# HV_DAC_8ch_FPGA_Config.net
KiCad netlist of a schematic drawn in Altium Designer
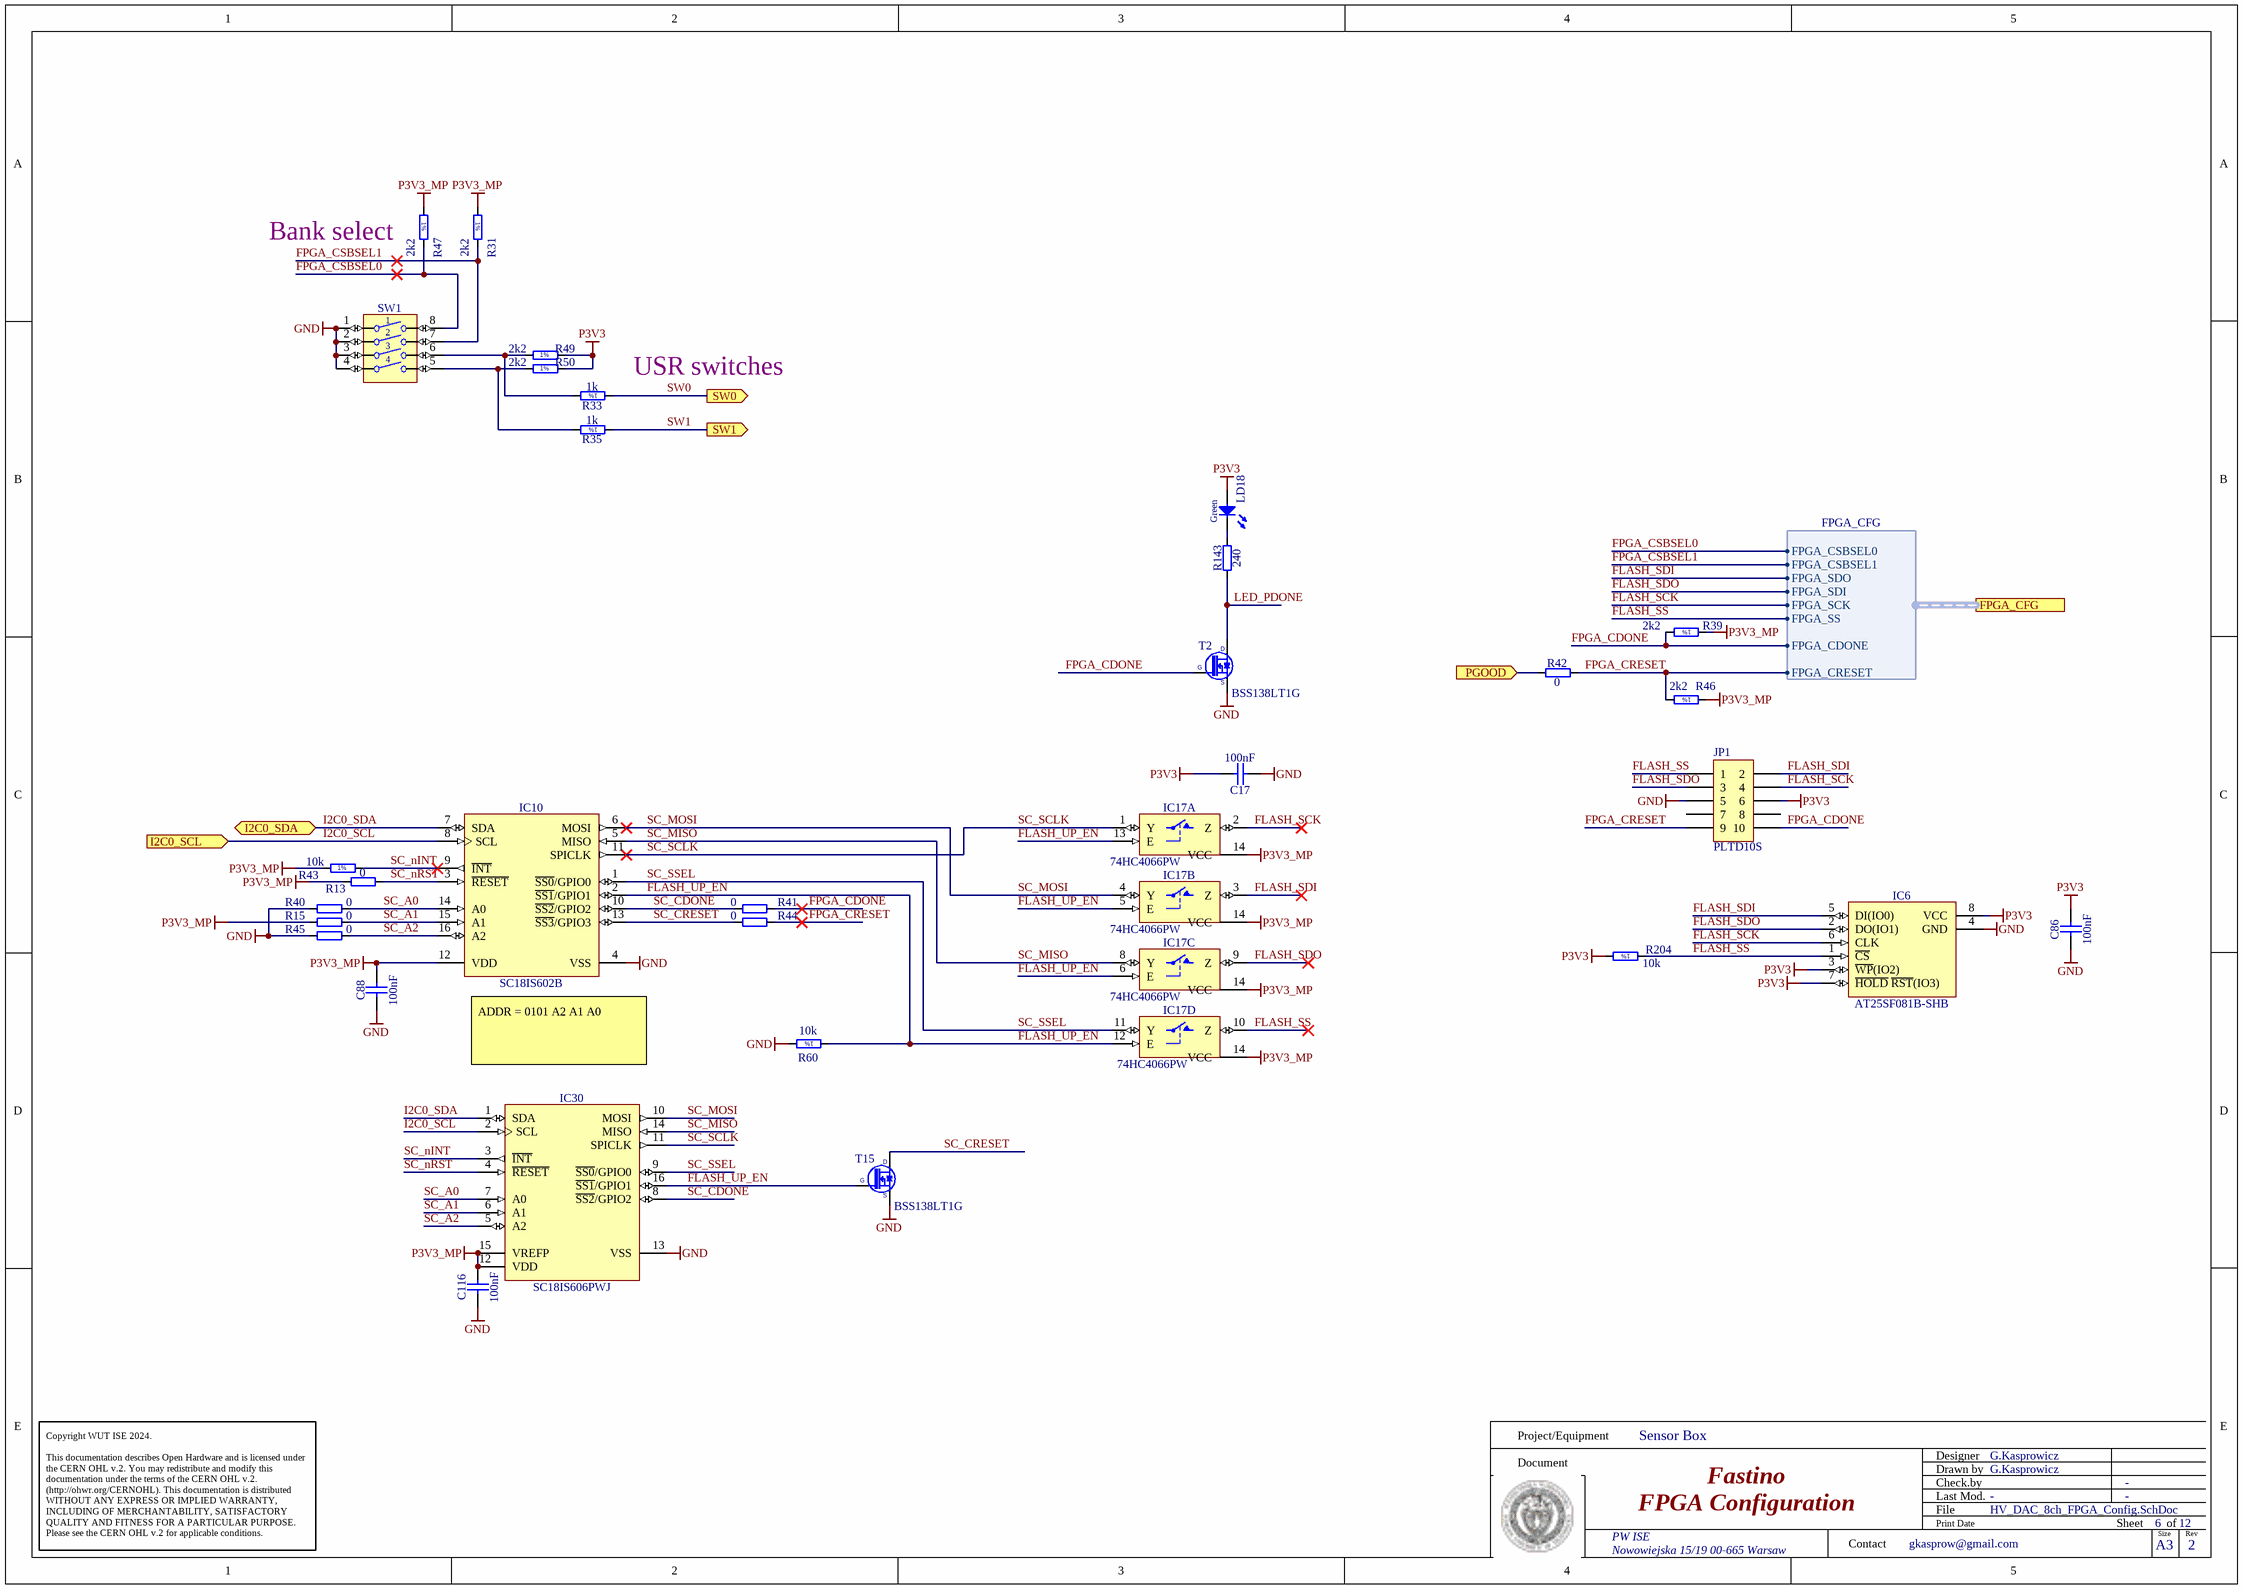
[diagram p0: HV_DAC_8ch_FPGA_Config.SchDoc]

(export (version "E")
  (design (tool "Eeschema 10.0.6"))
  (components
    (comp (ref "C17")
      (value "100nF")
      (footprint "CAPC1005X55N")
      (description "Non-polarised capacitor")
      (fields
        (field (name "PART NUMBER") "CC0402_100NF_16V_10%_X5R")
        (field (name "VOLTAGE") "16V")
        (field (name "AUTHOR") "CERN DEM JLC")
      )
      (libsource (lib "Capacitors") (part "Capacitor - non polarized"))
    )
    (comp (ref "C86")
      (value "100nF")
      (footprint "CAPC1005X55N")
      (description "Non-polarised capacitor")
      (fields
        (field (name "PART NUMBER") "CC0402_100NF_16V_10%_X5R")
        (field (name "VOLTAGE") "16V")
        (field (name "AUTHOR") "CERN DEM JLC")
      )
      (libsource (lib "Capacitors") (part "Capacitor - non polarized"))
    )
    (comp (ref "C88")
      (value "100nF")
      (footprint "CAPC1005X55N")
      (description "Non-polarised capacitor")
      (fields
        (field (name "PART NUMBER") "CC0402_100NF_16V_10%_X5R")
        (field (name "VOLTAGE") "16V")
        (field (name "AUTHOR") "CERN DEM JLC")
      )
      (libsource (lib "Capacitors") (part "Capacitor - non polarized"))
    )
    (comp (ref "C116")
      (value "100nF")
      (footprint "CAPC1005X55N")
      (description "Non-polarised capacitor")
      (fields
        (field (name "PART NUMBER") "CC0402_100NF_16V_10%_X5R")
        (field (name "VOLTAGE") "16V")
        (field (name "AUTHOR") "CERN DEM JLC")
      )
      (libsource (lib "Capacitors") (part "Capacitor - non polarized"))
    )
    (comp (ref "IC6")
      (value "AT25SF081B-SHB")
      (footprint "SOIC127P790X216-8N")
      (description "8M-bit Serial Flash Memory with uniform 4KB sectors and Dual/Quad SPI and QPI")
      (fields (field (name "MANUFACTURER") "Renesas") (field (name "AUTHOR") "GK"))
      (libsource (lib "ICS-logic") (part "MEM_AT25SF081B-SHB"))
    )
    (comp (ref "IC10")
      (value "SC18IS602B")
      (footprint "SOP65P640X110-16N")
      (description "I2C-bus to SPI bridge")
      (fields (field (name "MANUFACTURER") "NXP SEMICONDUCTORS") (field (name "AUTHOR") "CERN DEM MR"))
      (libsource (lib "ICs And Semiconductors") (part "SC18IS602B"))
    )
    (comp (ref "IC17")
      (value "74HC4066PW")
      (footprint "SOP65P640X110-14N")
      (fields (field (name "MANUFACTURER") "NXP SEMICONDUCTORS") (field (name "AUTHOR") "CERN DEM JLC"))
      (libsource (lib "ICs And Semiconductors") (part "4066"))
    )
    (comp (ref "IC30")
      (value "SC18IS606PWJ")
      (footprint "SOP65P640X110-16N")
      (description "I2C-bus to SPI bridge")
      (fields (field (name "MANUFACTURER") "NXP SEMICONDUCTORS") (field (name "AUTHOR") "GK"))
      (libsource (lib "ICS-logic") (part "SC18IS606PWJ"))
    )
    (comp (ref "JP1")
      (value "PLTD10S")
      (footprint "PLTD10S")
      (description "Goldpin 2.54mm, male header")
      (fields (field (name "MANUFACTURER") "Maritex"))
      (libsource (lib "LIBRARY_SCH") (part "CON_2x5 2.54 male SMT"))
    )
    (comp (ref "LD18")
      (value "Green")
      (footprint "LED_AVAGO_HSME-C120")
      (description "LED Green 1C 2A")
      (fields
        (field (name "PART NUMBER") "LED_AVAGO_HSME-C120")
        (field (name "MANUFACTURER") "AVAGO TECHNOLOGIES")
        (field (name "AUTHOR") "CERN DEM JMW")
      )
      (libsource (lib "ICs And Semiconductors") (part "LED Green 1C 2A"))
    )
    (comp (ref "R13")
      (value "0")
      (footprint "RESC1005X40N")
      (description "Resistor")
      (fields
        (field (name "PART NUMBER") "R0402_0R_JUMPER")
        (field (name "MANUFACTURER") "GENERIC")
        (field (name "AUTHOR") "CERN DEM JLC")
      )
      (libsource (lib "Resistors") (part "Resistor"))
    )
    (comp (ref "R15")
      (value "0")
      (footprint "RESC1005X40N")
      (description "Resistor")
      (fields
        (field (name "PART NUMBER") "R0402_0R_JUMPER")
        (field (name "MANUFACTURER") "GENERIC")
        (field (name "AUTHOR") "CERN DEM JLC")
      )
      (libsource (lib "Resistors") (part "Resistor"))
    )
    (comp (ref "R31")
      (value "2k2")
      (footprint "RESC1005X40N")
      (description "Resistor - 1%")
      (fields
        (field (name "PART NUMBER") "R0402_2K2_1%_0.0625W_100PPM")
        (field (name "POWER") "0.0625W")
        (field (name "AUTHOR") "CERN DEM JLC")
      )
      (libsource (lib "Resistors") (part "Resistor - 1%"))
    )
    (comp (ref "R33")
      (value "1k")
      (footprint "RESC1005X40N")
      (description "Resistor - 1%")
      (fields
        (field (name "PART NUMBER") "R0402_1K_1%_0.0625W_100PPM")
        (field (name "POWER") "0.0625W")
        (field (name "AUTHOR") "CERN DEM JLC")
      )
      (libsource (lib "Resistors") (part "Resistor - 1%"))
    )
    (comp (ref "R35")
      (value "1k")
      (footprint "RESC1005X40N")
      (description "Resistor - 1%")
      (fields
        (field (name "PART NUMBER") "R0402_1K_1%_0.0625W_100PPM")
        (field (name "POWER") "0.0625W")
        (field (name "AUTHOR") "CERN DEM JLC")
      )
      (libsource (lib "Resistors") (part "Resistor - 1%"))
    )
    (comp (ref "R39")
      (value "2k2")
      (footprint "RESC1005X40N")
      (description "Resistor - 1%")
      (fields
        (field (name "PART NUMBER") "R0402_2K2_1%_0.0625W_100PPM")
        (field (name "POWER") "0.0625W")
        (field (name "AUTHOR") "CERN DEM JLC")
      )
      (libsource (lib "Resistors") (part "Resistor - 1%"))
    )
    (comp (ref "R40")
      (value "0")
      (footprint "RESC1005X40N")
      (description "Resistor")
      (fields
        (field (name "PART NUMBER") "R0402_0R_JUMPER")
        (field (name "MANUFACTURER") "GENERIC")
        (field (name "AUTHOR") "CERN DEM JLC")
      )
      (libsource (lib "Resistors") (part "Resistor"))
    )
    (comp (ref "R41")
      (value "0")
      (footprint "RESC1005X40N")
      (description "Resistor")
      (fields
        (field (name "PART NUMBER") "R0402_0R_JUMPER")
        (field (name "MANUFACTURER") "GENERIC")
        (field (name "AUTHOR") "CERN DEM JLC")
      )
      (libsource (lib "Resistors") (part "Resistor"))
    )
    (comp (ref "R42")
      (value "0")
      (footprint "RESC1005X40N")
      (description "Resistor")
      (fields
        (field (name "PART NUMBER") "R0402_0R_JUMPER")
        (field (name "MANUFACTURER") "GENERIC")
        (field (name "AUTHOR") "CERN DEM JLC")
      )
      (libsource (lib "Resistors") (part "Resistor"))
    )
    (comp (ref "R43")
      (value "10k")
      (footprint "RESC1005X40N")
      (description "Resistor - 1%")
      (fields
        (field (name "PART NUMBER") "R0402_10K_1%_0.0625W_100PPM")
        (field (name "POWER") "0.0625W")
        (field (name "AUTHOR") "CERN DEM JLC")
      )
      (libsource (lib "Resistors") (part "Resistor - 1%"))
    )
    (comp (ref "R44")
      (value "0")
      (footprint "RESC1005X40N")
      (description "Resistor")
      (fields
        (field (name "PART NUMBER") "R0402_0R_JUMPER")
        (field (name "MANUFACTURER") "GENERIC")
        (field (name "AUTHOR") "CERN DEM JLC")
      )
      (libsource (lib "Resistors") (part "Resistor"))
    )
    (comp (ref "R45")
      (value "0")
      (footprint "RESC1005X40N")
      (description "Resistor")
      (fields
        (field (name "PART NUMBER") "R0402_0R_JUMPER")
        (field (name "MANUFACTURER") "GENERIC")
        (field (name "AUTHOR") "CERN DEM JLC")
      )
      (libsource (lib "Resistors") (part "Resistor"))
    )
    (comp (ref "R46")
      (value "2k2")
      (footprint "RESC1005X40N")
      (description "Resistor - 1%")
      (fields
        (field (name "PART NUMBER") "R0402_2K2_1%_0.0625W_100PPM")
        (field (name "POWER") "0.0625W")
        (field (name "AUTHOR") "CERN DEM JLC")
      )
      (libsource (lib "Resistors") (part "Resistor - 1%"))
    )
    (comp (ref "R47")
      (value "2k2")
      (footprint "RESC1005X40N")
      (description "Resistor - 1%")
      (fields
        (field (name "PART NUMBER") "R0402_2K2_1%_0.0625W_100PPM")
        (field (name "POWER") "0.0625W")
        (field (name "AUTHOR") "CERN DEM JLC")
      )
      (libsource (lib "Resistors") (part "Resistor - 1%"))
    )
    (comp (ref "R49")
      (value "2k2")
      (footprint "RESC1005X40N")
      (description "Resistor - 1%")
      (fields
        (field (name "PART NUMBER") "R0402_2K2_1%_0.0625W_100PPM")
        (field (name "POWER") "0.0625W")
        (field (name "AUTHOR") "CERN DEM JLC")
      )
      (libsource (lib "Resistors") (part "Resistor - 1%"))
    )
    (comp (ref "R50")
      (value "2k2")
      (footprint "RESC1005X40N")
      (description "Resistor - 1%")
      (fields
        (field (name "PART NUMBER") "R0402_2K2_1%_0.0625W_100PPM")
        (field (name "POWER") "0.0625W")
        (field (name "AUTHOR") "CERN DEM JLC")
      )
      (libsource (lib "Resistors") (part "Resistor - 1%"))
    )
    (comp (ref "R60")
      (value "10k")
      (footprint "RESC1005X40N")
      (description "Resistor - 1%")
      (fields
        (field (name "PART NUMBER") "R0402_10K_1%_0.0625W_100PPM")
        (field (name "POWER") "0.0625W")
        (field (name "AUTHOR") "CERN DEM JLC")
      )
      (libsource (lib "Resistors") (part "Resistor - 1%"))
    )
    (comp (ref "R143")
      (value "240")
      (footprint "RESC1005X40N")
      (description "Resistor - 1%")
      (fields
        (field (name "PART NUMBER") "R0402_240R_1%_0.0625W_100PPM")
        (field (name "POWER") "0.0625W")
        (field (name "AUTHOR") "CERN DEM JLC")
      )
      (libsource (lib "Resistors") (part "Resistor - 1%"))
    )
    (comp (ref "R204")
      (value "10k")
      (footprint "RESC1005X40N")
      (description "Resistor - 1%")
      (fields
        (field (name "PART NUMBER") "R0402_10K_1%_0.0625W_100PPM")
        (field (name "POWER") "0.0625W")
        (field (name "AUTHOR") "CERN DEM JLC")
      )
      (libsource (lib "Resistors") (part "Resistor - 1%"))
    )
    (comp (ref "SW1")
      (value "Switch")
      (footprint "SW_TYCO_1571983-4")
      (description "4 Ways SPST DIP Switch")
      (fields
        (field (name "PART NUMBER") "SW_TYCO_1571983-4")
        (field (name "MANUFACTURER") "TYCO")
        (field (name "AUTHOR") "CERN DEM JLC")
      )
      (libsource (lib "Eletro-mechanical") (part "SW 4x SPST DIP Switch"))
    )
    (comp (ref "T2")
      (value "BSS138LT1G")
      (footprint "SOT95P240X110-3N")
      (description "N-CHANNEL MOSFET WITH DIODE")
      (fields (field (name "MANUFACTURER") "ON SEMICONDUCTOR") (field (name "AUTHOR") "CERN DEM JLC"))
      (libsource (lib "ICs And Semiconductors") (part "N-MOSFET-D 1G 2S 3D"))
    )
    (comp (ref "T15")
      (value "BSS138LT1G")
      (footprint "SOT95P240X110-3N")
      (description "N-CHANNEL MOSFET WITH DIODE")
      (fields (field (name "MANUFACTURER") "ON SEMICONDUCTOR") (field (name "AUTHOR") "CERN DEM JLC"))
      (libsource (lib "ICs And Semiconductors") (part "N-MOSFET-D 1G 2S 3D"))
    )
  )
  (nets
    (net (code "2") (name "/FLASH_SCK") (class "Default")
      (node (ref "IC17") (pin "2") (pinfunction "Z_2") (pintype "bidirectional"))
      (node (ref "IC6") (pin "6") (pinfunction "CLK_6") (pintype "input"))
      (node (ref "JP1") (pin "4") (pinfunction "4_4") (pintype "passive"))
    )
    (net (code "3") (name "/FLASH_SDI") (class "Default")
      (node (ref "IC17") (pin "3") (pinfunction "Z_3") (pintype "bidirectional"))
      (node (ref "IC6") (pin "5") (pinfunction "DI(IO0)_5") (pintype "bidirectional"))
      (node (ref "JP1") (pin "2") (pinfunction "2_2") (pintype "passive"))
    )
    (net (code "4") (name "/FLASH_SDO") (class "Default")
      (node (ref "IC17") (pin "9") (pinfunction "Z_9") (pintype "bidirectional"))
      (node (ref "IC6") (pin "2") (pinfunction "DO(IO1)_2") (pintype "bidirectional"))
      (node (ref "JP1") (pin "3") (pinfunction "3_3") (pintype "passive"))
    )
    (net (code "5") (name "/FLASH_SS") (class "Default")
      (node (ref "IC17") (pin "10") (pinfunction "Z_10") (pintype "bidirectional"))
      (node (ref "IC6") (pin "1") (pinfunction "~{CS}_1") (pintype "input"))
      (node (ref "JP1") (pin "1") (pinfunction "1_1") (pintype "passive"))
      (node (ref "R204") (pin "1") (pinfunction "1_1") (pintype "passive"))
    )
    (net (code "6") (name "/FLASH_UP_EN") (class "Default")
      (node (ref "IC10") (pin "2") (pinfunction "~{SS1}/GPIO1_2") (pintype "bidirectional"))
      (node (ref "IC17") (pin "12") (pinfunction "E_12") (pintype "input"))
      (node (ref "IC17") (pin "13") (pinfunction "E_13") (pintype "input"))
      (node (ref "IC17") (pin "5") (pinfunction "E_5") (pintype "input"))
      (node (ref "IC17") (pin "6") (pinfunction "E_6") (pintype "input"))
      (node (ref "IC30") (pin "16") (pinfunction "~{SS1}/GPIO1_16") (pintype "bidirectional"))
      (node (ref "R60") (pin "1") (pinfunction "1_1") (pintype "passive"))
      (node (ref "T15") (pin "1") (pinfunction "G_1") (pintype "passive"))
    )
    (net (code "7") (name "/FPGA_CDONE") (class "Default")
      (node (ref "JP1") (pin "10") (pinfunction "10_10") (pintype "passive"))
      (node (ref "R39") (pin "2") (pinfunction "2_2") (pintype "passive"))
      (node (ref "R41") (pin "1") (pinfunction "1_1") (pintype "passive"))
      (node (ref "T2") (pin "1") (pinfunction "G_1") (pintype "passive"))
    )
    (net (code "8") (name "/FPGA_CRESET") (class "Default")
      (node (ref "JP1") (pin "9") (pinfunction "9_9") (pintype "passive"))
      (node (ref "R42") (pin "2") (pinfunction "2_2") (pintype "passive"))
      (node (ref "R44") (pin "1") (pinfunction "1_1") (pintype "passive"))
      (node (ref "R46") (pin "2") (pinfunction "2_2") (pintype "passive"))
    )
    (net (code "9") (name "/FPGA_CSBSEL0") (class "Default")
      (node (ref "R47") (pin "2") (pinfunction "2_2") (pintype "passive"))
      (node (ref "SW1") (pin "8") (pinfunction "8_8") (pintype "bidirectional"))
    )
    (net (code "10") (name "/FPGA_CSBSEL1") (class "Default")
      (node (ref "R31") (pin "2") (pinfunction "2_2") (pintype "passive"))
      (node (ref "SW1") (pin "7") (pinfunction "7_7") (pintype "bidirectional"))
    )
    (net (code "11") (name "/I2C0_SCL") (class "Default")
      (node (ref "IC10") (pin "8") (pinfunction "SCL_8") (pintype "input"))
      (node (ref "IC30") (pin "2") (pinfunction "SCL_2") (pintype "input"))
    )
    (net (code "12") (name "/I2C0_SDA") (class "Default")
      (node (ref "IC10") (pin "7") (pinfunction "SDA_7") (pintype "bidirectional"))
      (node (ref "IC30") (pin "1") (pinfunction "SDA_1") (pintype "bidirectional"))
    )
    (net (code "13") (name "/LED_PDONE") (class "Default")
      (node (ref "R143") (pin "1") (pinfunction "1_1") (pintype "passive"))
      (node (ref "T2") (pin "3") (pinfunction "D_3") (pintype "passive"))
    )
    (net (code "14") (name "/PGOOD") (class "Default")
      (node (ref "R42") (pin "1") (pinfunction "1_1") (pintype "passive"))
    )
    (net (code "15") (name "/SC_A0") (class "Default")
      (node (ref "IC10") (pin "14") (pinfunction "A0_14") (pintype "input"))
      (node (ref "IC30") (pin "7") (pinfunction "A0_7") (pintype "input"))
      (node (ref "R40") (pin "1") (pinfunction "1_1") (pintype "passive"))
    )
    (net (code "16") (name "/SC_A1") (class "Default")
      (node (ref "IC10") (pin "15") (pinfunction "A1_15") (pintype "input"))
      (node (ref "IC30") (pin "6") (pinfunction "A1_6") (pintype "input"))
      (node (ref "R15") (pin "1") (pinfunction "1_1") (pintype "passive"))
    )
    (net (code "17") (name "/SC_A2") (class "Default")
      (node (ref "IC10") (pin "16") (pinfunction "A2_16") (pintype "bidirectional"))
      (node (ref "IC30") (pin "5") (pinfunction "A2_5") (pintype "bidirectional"))
      (node (ref "R45") (pin "1") (pinfunction "1_1") (pintype "passive"))
    )
    (net (code "18") (name "/SC_CDONE") (class "Default")
      (node (ref "IC10") (pin "10") (pinfunction "~{SS2}/GPIO2_10") (pintype "bidirectional"))
      (node (ref "IC30") (pin "8") (pinfunction "~{SS2}/GPIO2_8") (pintype "bidirectional"))
      (node (ref "R41") (pin "2") (pinfunction "2_2") (pintype "passive"))
    )
    (net (code "19") (name "/SC_CRESET") (class "Default")
      (node (ref "IC10") (pin "13") (pinfunction "~{SS3}/GPIO3_13") (pintype "bidirectional"))
      (node (ref "R44") (pin "2") (pinfunction "2_2") (pintype "passive"))
      (node (ref "T15") (pin "3") (pinfunction "D_3") (pintype "passive"))
    )
    (net (code "20") (name "/SC_MISO") (class "Default")
      (node (ref "IC10") (pin "5") (pinfunction "MISO_5") (pintype "input"))
      (node (ref "IC17") (pin "8") (pinfunction "Y_8") (pintype "bidirectional"))
      (node (ref "IC30") (pin "14") (pinfunction "MISO_14") (pintype "input"))
    )
    (net (code "21") (name "/SC_MOSI") (class "Default")
      (node (ref "IC10") (pin "6") (pinfunction "MOSI_6") (pintype "output"))
      (node (ref "IC17") (pin "4") (pinfunction "Y_4") (pintype "bidirectional"))
      (node (ref "IC30") (pin "10") (pinfunction "MOSI_10") (pintype "output"))
    )
    (net (code "22") (name "/SC_SCLK") (class "Default")
      (node (ref "IC10") (pin "11") (pinfunction "SPICLK_11") (pintype "output"))
      (node (ref "IC17") (pin "1") (pinfunction "Y_1") (pintype "bidirectional"))
      (node (ref "IC30") (pin "11") (pinfunction "SPICLK_11") (pintype "output"))
    )
    (net (code "23") (name "/SC_SSEL") (class "Default")
      (node (ref "IC10") (pin "1") (pinfunction "~{SS0}/GPIO0_1") (pintype "bidirectional"))
      (node (ref "IC17") (pin "11") (pinfunction "Y_11") (pintype "bidirectional"))
      (node (ref "IC30") (pin "9") (pinfunction "~{SS0}/GPIO0_9") (pintype "bidirectional"))
    )
    (net (code "24") (name "/SC_nINT") (class "Default")
      (node (ref "IC10") (pin "9") (pinfunction "~{INT}_9") (pintype "output"))
      (node (ref "IC30") (pin "3") (pinfunction "~{INT}_3") (pintype "output"))
      (node (ref "R43") (pin "2") (pinfunction "2_2") (pintype "passive"))
    )
    (net (code "25") (name "/SC_nRST") (class "Default")
      (node (ref "IC10") (pin "3") (pinfunction "~{RESET}_3") (pintype "input"))
      (node (ref "IC30") (pin "4") (pinfunction "~{RESET}_4") (pintype "input"))
      (node (ref "R13") (pin "1") (pinfunction "1_1") (pintype "passive"))
    )
    (net (code "26") (name "/SW0") (class "Default")
      (node (ref "R33") (pin "1") (pinfunction "1_1") (pintype "passive"))
    )
    (net (code "27") (name "/SW1") (class "Default")
      (node (ref "R35") (pin "1") (pinfunction "1_1") (pintype "passive"))
    )
    (net (code "29") (name "GND") (class "Default")
      (node (ref "C116") (pin "1") (pinfunction "1_1") (pintype "passive"))
      (node (ref "C17") (pin "1") (pinfunction "1_1") (pintype "passive"))
      (node (ref "C86") (pin "1") (pinfunction "1_1") (pintype "passive"))
      (node (ref "C88") (pin "1") (pinfunction "1_1") (pintype "passive"))
      (node (ref "IC10") (pin "4") (pinfunction "VSS_4") (pintype "power_in"))
      (node (ref "IC17") (pin "7") (pinfunction "GND_7") (pintype "power_in"))
      (node (ref "IC30") (pin "13") (pinfunction "VSS_13") (pintype "power_in"))
      (node (ref "IC6") (pin "4") (pinfunction "GND_4") (pintype "power_in"))
      (node (ref "JP1") (pin "5") (pinfunction "5_5") (pintype "passive"))
      (node (ref "R40") (pin "2") (pinfunction "2_2") (pintype "passive"))
      (node (ref "R45") (pin "2") (pinfunction "2_2") (pintype "passive"))
      (node (ref "R60") (pin "2") (pinfunction "2_2") (pintype "passive"))
      (node (ref "SW1") (pin "1") (pinfunction "1_1") (pintype "bidirectional"))
      (node (ref "SW1") (pin "2") (pinfunction "2_2") (pintype "bidirectional"))
      (node (ref "SW1") (pin "3") (pinfunction "3_3") (pintype "bidirectional"))
      (node (ref "SW1") (pin "4") (pinfunction "4_4") (pintype "bidirectional"))
      (node (ref "T15") (pin "2") (pinfunction "S_2") (pintype "passive"))
      (node (ref "T2") (pin "2") (pinfunction "S_2") (pintype "passive"))
    )
    (net (code "30") (name "Net-(LD18-C)") (class "Default")
      (node (ref "LD18") (pin "1") (pinfunction "C_1") (pintype "passive"))
      (node (ref "R143") (pin "2") (pinfunction "2_2") (pintype "passive"))
    )
    (net (code "31") (name "Net-(R33-Pad2)") (class "Default")
      (node (ref "R33") (pin "2") (pinfunction "2_2") (pintype "passive"))
      (node (ref "R49") (pin "1") (pinfunction "1_1") (pintype "passive"))
      (node (ref "SW1") (pin "6") (pinfunction "6_6") (pintype "bidirectional"))
    )
    (net (code "32") (name "Net-(R35-Pad2)") (class "Default")
      (node (ref "R35") (pin "2") (pinfunction "2_2") (pintype "passive"))
      (node (ref "R50") (pin "1") (pinfunction "1_1") (pintype "passive"))
      (node (ref "SW1") (pin "5") (pinfunction "5_5") (pintype "bidirectional"))
    )
    (net (code "33") (name "P3V3") (class "Default")
      (node (ref "C17") (pin "2") (pinfunction "2_2") (pintype "passive"))
      (node (ref "C86") (pin "2") (pinfunction "2_2") (pintype "passive"))
      (node (ref "IC6") (pin "3") (pinfunction "~{WP}(IO2)_3") (pintype "bidirectional"))
      (node (ref "IC6") (pin "7") (pinfunction "~{HOLD}_~{RST}(IO3)_7") (pintype "bidirectional"))
      (node (ref "IC6") (pin "8") (pinfunction "VCC_8") (pintype "power_in"))
      (node (ref "JP1") (pin "6") (pinfunction "6_6") (pintype "passive"))
      (node (ref "LD18") (pin "2") (pinfunction "A_2") (pintype "passive"))
      (node (ref "R204") (pin "2") (pinfunction "2_2") (pintype "passive"))
      (node (ref "R49") (pin "2") (pinfunction "2_2") (pintype "passive"))
      (node (ref "R50") (pin "2") (pinfunction "2_2") (pintype "passive"))
    )
    (net (code "34") (name "P3V3_MP") (class "Default")
      (node (ref "C116") (pin "2") (pinfunction "2_2") (pintype "passive"))
      (node (ref "C88") (pin "2") (pinfunction "2_2") (pintype "passive"))
      (node (ref "IC10") (pin "12") (pinfunction "VDD_12") (pintype "power_in"))
      (node (ref "IC17") (pin "14") (pinfunction "VCC_14") (pintype "power_in"))
      (node (ref "IC30") (pin "12") (pinfunction "VDD_12") (pintype "power_in"))
      (node (ref "IC30") (pin "15") (pinfunction "VREFP_15") (pintype "power_in"))
      (node (ref "R13") (pin "2") (pinfunction "2_2") (pintype "passive"))
      (node (ref "R15") (pin "2") (pinfunction "2_2") (pintype "passive"))
      (node (ref "R31") (pin "1") (pinfunction "1_1") (pintype "passive"))
      (node (ref "R39") (pin "1") (pinfunction "1_1") (pintype "passive"))
      (node (ref "R43") (pin "1") (pinfunction "1_1") (pintype "passive"))
      (node (ref "R46") (pin "1") (pinfunction "1_1") (pintype "passive"))
      (node (ref "R47") (pin "1") (pinfunction "1_1") (pintype "passive"))
    )
    (net (code "35") (name "unconnected-(JP1-Pad7)") (class "Default")
      (node (ref "JP1") (pin "7") (pinfunction "7_7") (pintype "passive"))
    )
    (net (code "36") (name "unconnected-(JP1-Pad8)") (class "Default")
      (node (ref "JP1") (pin "8") (pinfunction "8_8") (pintype "passive"))
    )
  )
)
